# IMX_3_3_V_Analog_Power_Supply.net
KiCad netlist of a schematic drawn in Altium Designer
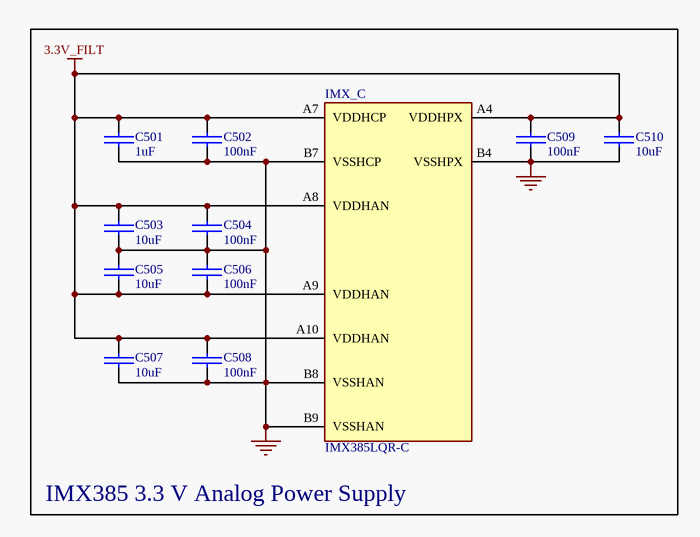
[diagram p0: IMX_3.3 V Analog Power Supply.SchDoc]

(export (version "E")
  (design (tool "Eeschema 10.0.6"))
  (components
    (comp (ref "C501")
      (value "1uF")
      (footprint "Capacitor, 0402")
      (description "Ceramic Capacitor, 10V, 10% +/- Tol, X7R, 1uF, SMD, 0402, #GRM155Z71A105KE01D, JLC#C528974")
      (libsource (lib "Component Library") (part "Capacitor, 0402, 1uF"))
    )
    (comp (ref "C502")
      (value "100nF")
      (footprint "Capacitor, 0402")
      (description "Ceramic Capacitor, 16V, 10% +/- Tol, X7R, 0.1uF, SMD, 0402, #CL05B104KO5NNNC, JLC#C1525")
      (libsource (lib "Component Library") (part "Capacitor, 0402, 100nF"))
    )
    (comp (ref "C503")
      (value "10uF")
      (footprint "Capacitor, 0603")
      (description "Ceramic Capacitor, 10V, 10% +/- Tol, X7R, 10uF, SMD, 0603, #GRM188Z71A106KA73D, JLC#C2959727")
      (libsource (lib "Component Library") (part "Capacitor, 0603, 10uF"))
    )
    (comp (ref "C504")
      (value "100nF")
      (footprint "Capacitor, 0402")
      (description "Ceramic Capacitor, 16V, 10% +/- Tol, X7R, 0.1uF, SMD, 0402, #CL05B104KO5NNNC, JLC#C1525")
      (libsource (lib "Component Library") (part "Capacitor, 0402, 100nF"))
    )
    (comp (ref "C505")
      (value "10uF")
      (footprint "Capacitor, 0603")
      (description "Ceramic Capacitor, 10V, 10% +/- Tol, X7R, 10uF, SMD, 0603, #GRM188Z71A106KA73D, JLC#C2959727")
      (libsource (lib "Component Library") (part "Capacitor, 0603, 10uF"))
    )
    (comp (ref "C506")
      (value "100nF")
      (footprint "Capacitor, 0402")
      (description "Ceramic Capacitor, 16V, 10% +/- Tol, X7R, 0.1uF, SMD, 0402, #CL05B104KO5NNNC, JLC#C1525")
      (libsource (lib "Component Library") (part "Capacitor, 0402, 100nF"))
    )
    (comp (ref "C507")
      (value "10uF")
      (footprint "Capacitor, 0603")
      (description "Ceramic Capacitor, 10V, 10% +/- Tol, X7R, 10uF, SMD, 0603, #GRM188Z71A106KA73D, JLC#C2959727")
      (libsource (lib "Component Library") (part "Capacitor, 0603, 10uF"))
    )
    (comp (ref "C508")
      (value "100nF")
      (footprint "Capacitor, 0402")
      (description "Ceramic Capacitor, 16V, 10% +/- Tol, X7R, 0.1uF, SMD, 0402, #CL05B104KO5NNNC, JLC#C1525")
      (libsource (lib "Component Library") (part "Capacitor, 0402, 100nF"))
    )
    (comp (ref "C509")
      (value "100nF")
      (footprint "Capacitor, 0402")
      (description "Ceramic Capacitor, 16V, 10% +/- Tol, X7R, 0.1uF, SMD, 0402, #CL05B104KO5NNNC, JLC#C1525")
      (libsource (lib "Component Library") (part "Capacitor, 0402, 100nF"))
    )
    (comp (ref "C510")
      (value "10uF")
      (footprint "Capacitor, 0603")
      (description "Ceramic Capacitor, 10V, 10% +/- Tol, X7R, 10uF, SMD, 0603, #GRM188Z71A106KA73D, JLC#C2959727")
      (libsource (lib "Component Library") (part "Capacitor, 0603, 10uF"))
    )
    (comp (ref "IMX_")
      (value "IMX385LQR-C")
      (footprint "IMX385LQR")
      (libsource (lib "Component Library") (part "IMX385LQR"))
    )
  )
  (nets
    (net (code "1") (name "3.3V_FILT") (class "Default")
      (node (ref "C501") (pin "1") (pinfunction "1_1") (pintype "passive"))
      (node (ref "C502") (pin "1") (pinfunction "1_1") (pintype "passive"))
      (node (ref "C503") (pin "1") (pinfunction "1_1") (pintype "passive"))
      (node (ref "C504") (pin "1") (pinfunction "1_1") (pintype "passive"))
      (node (ref "C505") (pin "2") (pinfunction "2_2") (pintype "passive"))
      (node (ref "C506") (pin "2") (pinfunction "2_2") (pintype "passive"))
      (node (ref "C507") (pin "1") (pinfunction "1_1") (pintype "passive"))
      (node (ref "C508") (pin "1") (pinfunction "1_1") (pintype "passive"))
      (node (ref "C509") (pin "1") (pinfunction "1_1") (pintype "passive"))
      (node (ref "C510") (pin "1") (pinfunction "1_1") (pintype "passive"))
      (node (ref "IMX_") (pin "A10") (pinfunction "VDDHAN_A10") (pintype "passive"))
      (node (ref "IMX_") (pin "A4") (pinfunction "VDDHPX_A4") (pintype "passive"))
      (node (ref "IMX_") (pin "A7") (pinfunction "VDDHCP_A7") (pintype "passive"))
      (node (ref "IMX_") (pin "A8") (pinfunction "VDDHAN_A8") (pintype "passive"))
      (node (ref "IMX_") (pin "A9") (pinfunction "VDDHAN_A9") (pintype "passive"))
    )
    (net (code "2") (name "GND") (class "Default")
      (node (ref "C501") (pin "2") (pinfunction "2_2") (pintype "passive"))
      (node (ref "C502") (pin "2") (pinfunction "2_2") (pintype "passive"))
      (node (ref "C503") (pin "2") (pinfunction "2_2") (pintype "passive"))
      (node (ref "C504") (pin "2") (pinfunction "2_2") (pintype "passive"))
      (node (ref "C505") (pin "1") (pinfunction "1_1") (pintype "passive"))
      (node (ref "C506") (pin "1") (pinfunction "1_1") (pintype "passive"))
      (node (ref "C507") (pin "2") (pinfunction "2_2") (pintype "passive"))
      (node (ref "C508") (pin "2") (pinfunction "2_2") (pintype "passive"))
      (node (ref "C509") (pin "2") (pinfunction "2_2") (pintype "passive"))
      (node (ref "C510") (pin "2") (pinfunction "2_2") (pintype "passive"))
      (node (ref "IMX_") (pin "B4") (pinfunction "VSSHPX_B4") (pintype "passive"))
      (node (ref "IMX_") (pin "B7") (pinfunction "VSSHCP_B7") (pintype "passive"))
      (node (ref "IMX_") (pin "B8") (pinfunction "VSSHAN_B8") (pintype "passive"))
      (node (ref "IMX_") (pin "B9") (pinfunction "VSSHAN_B9") (pintype "passive"))
    )
  )
)
